# Nucleo_connections.net
KiCad netlist of a schematic drawn in Altium Designer
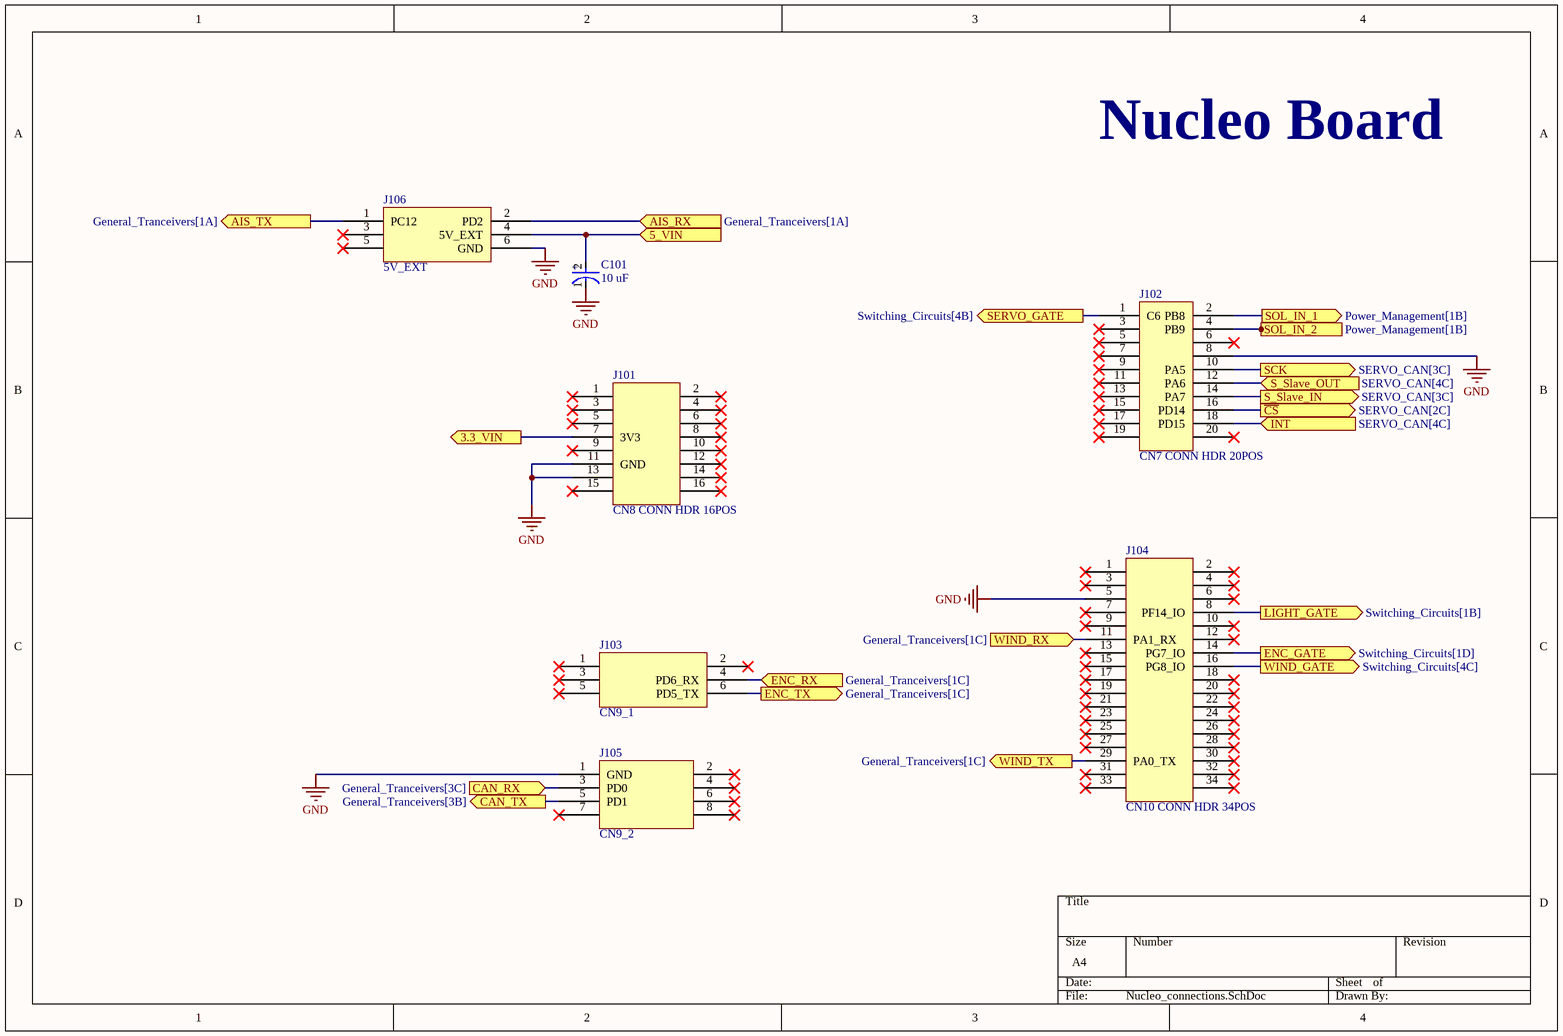
[diagram p0: Nucleo_connections.SchDoc]

(export (version "E")
  (design (tool "Eeschema 10.0.6"))
  (components
    (comp (ref "C101")
      (value "10 uF")
      (footprint "FP-RAD-TH-D_10_0_5-L_20_2-MFG")
      (description "Aluminum Electrolytic Capacitors (Radial Lead Type) 10uF ±20% 350V")
      (fields (field (name "TOLERANCE") "20%"))
      (libsource (lib "Altium Content Vault") (part "203bc49f2ac43e59fd269a8c329ed05"))
    )
    (comp (ref "J101")
      (value "CN8 CONN HDR 16POS")
      (footprint "CN8_8X2_PADS")
      (description "CN8 CONN HDR 16POS 0.1 STACK")
      (libsource (lib "Schlib2") (part "CN8 CONN HDR 16POS"))
    )
    (comp (ref "J102")
      (value "CN7 CONN HDR 20POS")
      (footprint "CN7_10X2_PADS")
      (description "CN7 CONN HDR 20 POS  0.1 STACK")
      (libsource (lib "Schlib1") (part "CN7 CONN HDR 20POS"))
    )
    (comp (ref "J103") (value "CN9_1") (footprint "5V_EXT") (libsource (lib "Schlib1") (part "5V_EXT")))
    (comp (ref "J104")
      (value "CN10 CONN HDR 34POS")
      (footprint "CN10_17X2_PADS")
      (description "CN10 CONN HDR 34 POS  0.1 STACK")
      (libsource (lib "Schlib2") (part "CN10 CONN HDR 34POS"))
    )
    (comp (ref "J105") (value "CN9_2") (footprint "4x2") (libsource (lib "Schlib2") (part "4x2")))
    (comp (ref "J106") (value "5V_EXT") (footprint "5V_EXT") (libsource (lib "Schlib1") (part "5V_EXT")))
  )
  (nets
    (net (code "1") (name "/3.3_VIN") (class "Default")
      (node (ref "J101") (pin "7") (pinfunction "3V3_7") (pintype "passive"))
    )
    (net (code "2") (name "/5_VIN") (class "Default")
      (node (ref "C101") (pin "2") (pinfunction "A_2") (pintype "passive"))
      (node (ref "J106") (pin "4") (pinfunction "5V_EXT_4") (pintype "passive"))
    )
    (net (code "3") (name "/AIS_RX") (class "Default")
      (node (ref "J106") (pin "2") (pinfunction "PD2_2") (pintype "passive"))
    )
    (net (code "4") (name "/AIS_TX") (class "Default")
      (node (ref "J106") (pin "1") (pinfunction "PC12_1") (pintype "passive"))
    )
    (net (code "5") (name "/CAN_RX") (class "Default")
      (node (ref "J105") (pin "3") (pinfunction "PD0_3") (pintype "passive"))
    )
    (net (code "6") (name "/CAN_TX") (class "Default")
      (node (ref "J105") (pin "5") (pinfunction "PD1_5") (pintype "passive"))
    )
    (net (code "7") (name "/ENC_GATE") (class "Default")
      (node (ref "J104") (pin "14") (pinfunction "PG7_IO_14") (pintype "passive"))
    )
    (net (code "8") (name "/ENC_RX") (class "Default")
      (node (ref "J103") (pin "4") (pinfunction "5V_EXT_4") (pintype "passive"))
    )
    (net (code "9") (name "/ENC_TX") (class "Default")
      (node (ref "J103") (pin "6") (pinfunction "GND_6") (pintype "passive"))
    )
    (net (code "10") (name "/INT") (class "Default")
      (node (ref "J102") (pin "18") (pinfunction "PD15_18") (pintype "passive"))
    )
    (net (code "11") (name "/LIGHT_GATE") (class "Default")
      (node (ref "J104") (pin "8") (pinfunction "PF14_IO_8") (pintype "passive"))
    )
    (net (code "12") (name "/SCK") (class "Default")
      (node (ref "J102") (pin "10") (pinfunction "PA5_10") (pintype "passive"))
    )
    (net (code "13") (name "/SERVO_GATE") (class "Default")
      (node (ref "J102") (pin "1") (pinfunction "C6_1") (pintype "passive"))
    )
    (net (code "14") (name "/SOL_IN_1") (class "Default")
      (node (ref "J102") (pin "2") (pinfunction "PB8_2") (pintype "passive"))
    )
    (net (code "15") (name "/SOL_IN_2") (class "Default")
      (node (ref "J102") (pin "4") (pinfunction "PB9_4") (pintype "passive"))
    )
    (net (code "16") (name "/S_Slave_IN") (class "Default")
      (node (ref "J102") (pin "14") (pinfunction "PA7_14") (pintype "passive"))
    )
    (net (code "17") (name "/S_Slave_OUT") (class "Default")
      (node (ref "J102") (pin "12") (pinfunction "PA6_12") (pintype "passive"))
    )
    (net (code "18") (name "/WIND_GATE") (class "Default")
      (node (ref "J104") (pin "16") (pinfunction "PG8_IO_16") (pintype "passive"))
    )
    (net (code "19") (name "/WIND_RX") (class "Default")
      (node (ref "J104") (pin "11") (pinfunction "PA1_RX_11") (pintype "passive"))
    )
    (net (code "20") (name "/WIND_TX") (class "Default")
      (node (ref "J104") (pin "29") (pinfunction "PA0_TX_29") (pintype "passive"))
    )
    (net (code "21") (name "/~{CS}") (class "Default")
      (node (ref "J102") (pin "16") (pinfunction "PD14_16") (pintype "passive"))
    )
    (net (code "22") (name "GND") (class "Default")
      (node (ref "C101") (pin "1") (pinfunction "C_1") (pintype "passive"))
      (node (ref "J101") (pin "11") (pinfunction "GND_11") (pintype "passive"))
      (node (ref "J101") (pin "13") (pinfunction "GND_13") (pintype "passive"))
      (node (ref "J102") (pin "8") (pinfunction "8_8") (pintype "passive"))
      (node (ref "J104") (pin "5") (pinfunction "5_5") (pintype "passive"))
      (node (ref "J105") (pin "1") (pinfunction "GND_1") (pintype "passive"))
      (node (ref "J106") (pin "6") (pinfunction "GND_6") (pintype "passive"))
    )
    (net (code "23") (name "unconnected-(J101-PF3_IO-Pad14)") (class "Default")
      (node (ref "J101") (pin "14") (pinfunction "PF3_IO_14") (pintype "passive+no_connect"))
    )
    (net (code "24") (name "unconnected-(J101-PF5_IO-Pad16)") (class "Default")
      (node (ref "J101") (pin "16") (pinfunction "PF5_IO_16") (pintype "passive+no_connect"))
    )
    (net (code "25") (name "unconnected-(J101-Pad1)") (class "Default")
      (node (ref "J101") (pin "1") (pinfunction "1_1") (pintype "passive+no_connect"))
    )
    (net (code "26") (name "unconnected-(J101-Pad2)") (class "Default")
      (node (ref "J101") (pin "2") (pinfunction "2_2") (pintype "passive+no_connect"))
    )
    (net (code "27") (name "unconnected-(J101-Pad3)") (class "Default")
      (node (ref "J101") (pin "3") (pinfunction "3_3") (pintype "passive+no_connect"))
    )
    (net (code "28") (name "unconnected-(J101-Pad4)") (class "Default")
      (node (ref "J101") (pin "4") (pinfunction "4_4") (pintype "passive+no_connect"))
    )
    (net (code "29") (name "unconnected-(J101-Pad5)") (class "Default")
      (node (ref "J101") (pin "5") (pinfunction "5_5") (pintype "passive+no_connect"))
    )
    (net (code "30") (name "unconnected-(J101-Pad6)") (class "Default")
      (node (ref "J101") (pin "6") (pinfunction "6_6") (pintype "passive+no_connect"))
    )
    (net (code "31") (name "unconnected-(J101-Pad8)") (class "Default")
      (node (ref "J101") (pin "8") (pinfunction "8_8") (pintype "passive+no_connect"))
    )
    (net (code "32") (name "unconnected-(J101-Pad9)") (class "Default")
      (node (ref "J101") (pin "9") (pinfunction "9_9") (pintype "passive+no_connect"))
    )
    (net (code "33") (name "unconnected-(J101-Pad10)") (class "Default")
      (node (ref "J101") (pin "10") (pinfunction "10_10") (pintype "passive+no_connect"))
    )
    (net (code "34") (name "unconnected-(J101-Pad12)") (class "Default")
      (node (ref "J101") (pin "12") (pinfunction "12_12") (pintype "passive+no_connect"))
    )
    (net (code "35") (name "unconnected-(J101-VIN-Pad15)") (class "Default")
      (node (ref "J101") (pin "15") (pinfunction "VIN_15") (pintype "passive+no_connect"))
    )
    (net (code "36") (name "unconnected-(J102-Pad3)") (class "Default")
      (node (ref "J102") (pin "3") (pinfunction "3_3") (pintype "passive+no_connect"))
    )
    (net (code "37") (name "unconnected-(J102-Pad5)") (class "Default")
      (node (ref "J102") (pin "5") (pinfunction "5_5") (pintype "passive+no_connect"))
    )
    (net (code "38") (name "unconnected-(J102-Pad6)") (class "Default")
      (node (ref "J102") (pin "6") (pinfunction "6_6") (pintype "passive+no_connect"))
    )
    (net (code "39") (name "unconnected-(J102-Pad7)") (class "Default")
      (node (ref "J102") (pin "7") (pinfunction "7_7") (pintype "passive+no_connect"))
    )
    (net (code "40") (name "unconnected-(J102-Pad9)") (class "Default")
      (node (ref "J102") (pin "9") (pinfunction "9_9") (pintype "passive+no_connect"))
    )
    (net (code "41") (name "unconnected-(J102-Pad11)") (class "Default")
      (node (ref "J102") (pin "11") (pinfunction "11_11") (pintype "passive+no_connect"))
    )
    (net (code "42") (name "unconnected-(J102-Pad13)") (class "Default")
      (node (ref "J102") (pin "13") (pinfunction "13_13") (pintype "passive+no_connect"))
    )
    (net (code "43") (name "unconnected-(J102-Pad15)") (class "Default")
      (node (ref "J102") (pin "15") (pinfunction "15_15") (pintype "passive+no_connect"))
    )
    (net (code "44") (name "unconnected-(J102-Pad17)") (class "Default")
      (node (ref "J102") (pin "17") (pinfunction "17_17") (pintype "passive+no_connect"))
    )
    (net (code "45") (name "unconnected-(J102-Pad19)") (class "Default")
      (node (ref "J102") (pin "19") (pinfunction "19_19") (pintype "passive+no_connect"))
    )
    (net (code "46") (name "unconnected-(J102-Pad20)") (class "Default")
      (node (ref "J102") (pin "20") (pinfunction "20_20") (pintype "passive+no_connect"))
    )
    (net (code "47") (name "unconnected-(J103-7-Pad5)") (class "Default")
      (node (ref "J103") (pin "5") (pinfunction "7_5") (pintype "passive+no_connect"))
    )
    (net (code "48") (name "unconnected-(J103-PC12-Pad1)") (class "Default")
      (node (ref "J103") (pin "1") (pinfunction "PC12_1") (pintype "passive+no_connect"))
    )
    (net (code "49") (name "unconnected-(J103-PD2-Pad2)") (class "Default")
      (node (ref "J103") (pin "2") (pinfunction "PD2_2") (pintype "passive+no_connect"))
    )
    (net (code "50") (name "unconnected-(J103-VDD-Pad3)") (class "Default")
      (node (ref "J103") (pin "3") (pinfunction "VDD_3") (pintype "passive+no_connect"))
    )
    (net (code "51") (name "unconnected-(J104-Pad1)") (class "Default")
      (node (ref "J104") (pin "1") (pinfunction "1_1") (pintype "passive+no_connect"))
    )
    (net (code "52") (name "unconnected-(J104-Pad2)") (class "Default")
      (node (ref "J104") (pin "2") (pinfunction "2_2") (pintype "passive+no_connect"))
    )
    (net (code "53") (name "unconnected-(J104-Pad3)") (class "Default")
      (node (ref "J104") (pin "3") (pinfunction "3_3") (pintype "passive+no_connect"))
    )
    (net (code "54") (name "unconnected-(J104-Pad4)") (class "Default")
      (node (ref "J104") (pin "4") (pinfunction "4_4") (pintype "passive+no_connect"))
    )
    (net (code "55") (name "unconnected-(J104-Pad6)") (class "Default")
      (node (ref "J104") (pin "6") (pinfunction "6_6") (pintype "passive+no_connect"))
    )
    (net (code "56") (name "unconnected-(J104-Pad7)") (class "Default")
      (node (ref "J104") (pin "7") (pinfunction "7_7") (pintype "passive+no_connect"))
    )
    (net (code "57") (name "unconnected-(J104-Pad9)") (class "Default")
      (node (ref "J104") (pin "9") (pinfunction "9_9") (pintype "passive+no_connect"))
    )
    (net (code "58") (name "unconnected-(J104-Pad10)") (class "Default")
      (node (ref "J104") (pin "10") (pinfunction "10_10") (pintype "passive+no_connect"))
    )
    (net (code "59") (name "unconnected-(J104-Pad12)") (class "Default")
      (node (ref "J104") (pin "12") (pinfunction "12_12") (pintype "passive+no_connect"))
    )
    (net (code "60") (name "unconnected-(J104-Pad13)") (class "Default")
      (node (ref "J104") (pin "13") (pinfunction "13_13") (pintype "passive+no_connect"))
    )
    (net (code "61") (name "unconnected-(J104-Pad15)") (class "Default")
      (node (ref "J104") (pin "15") (pinfunction "15_15") (pintype "passive+no_connect"))
    )
    (net (code "62") (name "unconnected-(J104-Pad17)") (class "Default")
      (node (ref "J104") (pin "17") (pinfunction "17_17") (pintype "passive+no_connect"))
    )
    (net (code "63") (name "unconnected-(J104-Pad18)") (class "Default")
      (node (ref "J104") (pin "18") (pinfunction "18_18") (pintype "passive+no_connect"))
    )
    (net (code "64") (name "unconnected-(J104-Pad19)") (class "Default")
      (node (ref "J104") (pin "19") (pinfunction "19_19") (pintype "passive+no_connect"))
    )
    (net (code "65") (name "unconnected-(J104-Pad20)") (class "Default")
      (node (ref "J104") (pin "20") (pinfunction "20_20") (pintype "passive+no_connect"))
    )
    (net (code "66") (name "unconnected-(J104-Pad21)") (class "Default")
      (node (ref "J104") (pin "21") (pinfunction "21_21") (pintype "passive+no_connect"))
    )
    (net (code "67") (name "unconnected-(J104-Pad22)") (class "Default")
      (node (ref "J104") (pin "22") (pinfunction "22_22") (pintype "passive+no_connect"))
    )
    (net (code "68") (name "unconnected-(J104-Pad23)") (class "Default")
      (node (ref "J104") (pin "23") (pinfunction "23_23") (pintype "passive+no_connect"))
    )
    (net (code "69") (name "unconnected-(J104-Pad24)") (class "Default")
      (node (ref "J104") (pin "24") (pinfunction "24_24") (pintype "passive+no_connect"))
    )
    (net (code "70") (name "unconnected-(J104-Pad25)") (class "Default")
      (node (ref "J104") (pin "25") (pinfunction "25_25") (pintype "passive+no_connect"))
    )
    (net (code "71") (name "unconnected-(J104-Pad26)") (class "Default")
      (node (ref "J104") (pin "26") (pinfunction "26_26") (pintype "passive+no_connect"))
    )
    (net (code "72") (name "unconnected-(J104-Pad27)") (class "Default")
      (node (ref "J104") (pin "27") (pinfunction "27_27") (pintype "passive+no_connect"))
    )
    (net (code "73") (name "unconnected-(J104-Pad28)") (class "Default")
      (node (ref "J104") (pin "28") (pinfunction "28_28") (pintype "passive+no_connect"))
    )
    (net (code "74") (name "unconnected-(J104-Pad30)") (class "Default")
      (node (ref "J104") (pin "30") (pinfunction "30_30") (pintype "passive+no_connect"))
    )
    (net (code "75") (name "unconnected-(J104-Pad31)") (class "Default")
      (node (ref "J104") (pin "31") (pinfunction "31_31") (pintype "passive+no_connect"))
    )
    (net (code "76") (name "unconnected-(J104-Pad32)") (class "Default")
      (node (ref "J104") (pin "32") (pinfunction "32_32") (pintype "passive+no_connect"))
    )
    (net (code "77") (name "unconnected-(J104-Pad33)") (class "Default")
      (node (ref "J104") (pin "33") (pinfunction "33_33") (pintype "passive+no_connect"))
    )
    (net (code "78") (name "unconnected-(J104-Pad34)") (class "Default")
      (node (ref "J104") (pin "34") (pinfunction "34_34") (pintype "passive+no_connect"))
    )
    (net (code "79") (name "unconnected-(J105-Pad2)") (class "Default")
      (node (ref "J105") (pin "2") (pinfunction "2_2") (pintype "passive+no_connect"))
    )
    (net (code "80") (name "unconnected-(J105-Pad4)") (class "Default")
      (node (ref "J105") (pin "4") (pinfunction "4_4") (pintype "passive+no_connect"))
    )
    (net (code "81") (name "unconnected-(J105-Pad6)") (class "Default")
      (node (ref "J105") (pin "6") (pinfunction "6_6") (pintype "passive+no_connect"))
    )
    (net (code "82") (name "unconnected-(J105-Pad7)") (class "Default")
      (node (ref "J105") (pin "7") (pinfunction "7_7") (pintype "passive+no_connect"))
    )
    (net (code "83") (name "unconnected-(J105-Pad8)") (class "Default")
      (node (ref "J105") (pin "8") (pinfunction "8_8") (pintype "passive+no_connect"))
    )
    (net (code "84") (name "unconnected-(J106-7-Pad5)") (class "Default")
      (node (ref "J106") (pin "5") (pinfunction "7_5") (pintype "passive+no_connect"))
    )
    (net (code "85") (name "unconnected-(J106-VDD-Pad3)") (class "Default")
      (node (ref "J106") (pin "3") (pinfunction "VDD_3") (pintype "passive+no_connect"))
    )
  )
)
